# 13-UWB-Antenna.net
KiCad netlist of a schematic drawn in Altium Designer
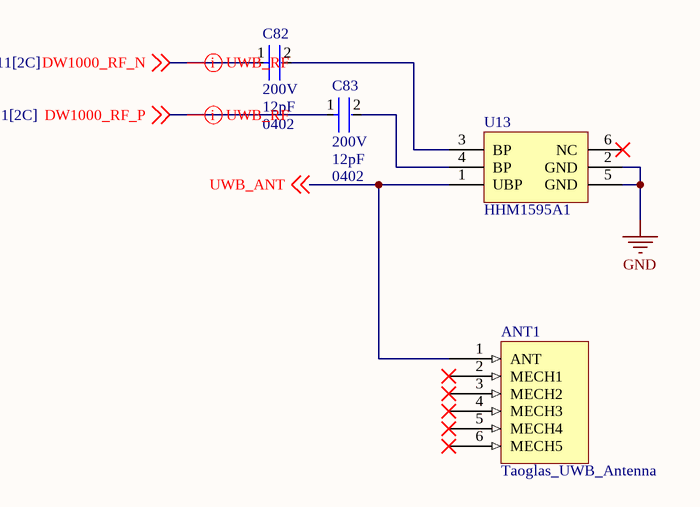
[diagram p0: 13-UWB-Antenna.SchDoc]

(export (version "E")
  (design (tool "Eeschema 10.0.6"))
  (components
    (comp (ref "ANT1")
      (value "Taoglas_UWB_Antenna")
      (footprint "UWC.20 Antenna")
      (libsource (lib "TimeDrive_Lib") (part "Taoglas_UWB_Antenna"))
    )
    (comp (ref "C82")
      (value "GQM1555C2D120FB01D")
      (footprint "FP-GQM155-0_05-MFG")
      (description "Ceramic Capacitor 12pF  ±1% 200VDC C0G 0402 Paper T/R")
      (fields
        (field (name "VOLTAGE RATING (DC)") "200V")
        (field (name "TOLERANCE") "1%")
        (field (name "CAPACITANCE") "12pF")
        (field (name "CASE/PACKAGE") "0402")
      )
      (libsource (lib "Altium Content Vault") (part "11868f565c42a9108669ba33697ecf6"))
    )
    (comp (ref "C83")
      (value "GQM1555C2D120FB01D")
      (footprint "FP-GQM155-0_05-MFG")
      (description "Ceramic Capacitor 12pF  ±1% 200VDC C0G 0402 Paper T/R")
      (fields
        (field (name "VOLTAGE RATING (DC)") "200V")
        (field (name "TOLERANCE") "1%")
        (field (name "CAPACITANCE") "12pF")
        (field (name "CASE/PACKAGE") "0402")
      )
      (libsource (lib "Altium Content Vault") (part "11868f565c42a9108669ba33697ecf6"))
    )
    (comp (ref "U13")
      (value "HHM1595A1")
      (footprint "TDK-HHM1595A1_V")
      (description "Multilayer Balun, 3000 to 8000 MHz, -40 to 85 degC, 6-Pin SMD, RoHS, Tape and Reel")
      (fields (field (name "MANUFACTURER") "TDK"))
      (libsource (lib "Altium Content Vault") (part "TDK-HHM1595A1-6"))
    )
  )
  (nets
    (net (code "1") (name "DW1000_RF_N") (class "Default")
      (node (ref "C82") (pin "1") (pinfunction "1_1") (pintype "passive"))
    )
    (net (code "2") (name "DW1000_RF_P") (class "Default")
      (node (ref "C83") (pin "1") (pinfunction "1_1") (pintype "passive"))
    )
    (net (code "3") (name "GND") (class "Default")
      (node (ref "U13") (pin "2") (pinfunction "GND_2") (pintype "power_in"))
      (node (ref "U13") (pin "5") (pinfunction "GND_5") (pintype "power_in"))
    )
    (net (code "4") (name "Net-(C82-Pad2)") (class "Default")
      (node (ref "C82") (pin "2") (pinfunction "2_2") (pintype "passive"))
      (node (ref "U13") (pin "3") (pinfunction "BP_3") (pintype "passive"))
    )
    (net (code "5") (name "Net-(C83-Pad2)") (class "Default")
      (node (ref "C83") (pin "2") (pinfunction "2_2") (pintype "passive"))
      (node (ref "U13") (pin "4") (pinfunction "BP_4") (pintype "passive"))
    )
    (net (code "6") (name "UWB_ANT") (class "Default")
      (node (ref "ANT1") (pin "1") (pinfunction "ANT_1") (pintype "input"))
      (node (ref "U13") (pin "1") (pinfunction "UBP_1") (pintype "passive"))
    )
    (net (code "7") (name "unconnected-(ANT1-MECH1-Pad2)") (class "Default")
      (node (ref "ANT1") (pin "2") (pinfunction "MECH1_2") (pintype "input+no_connect"))
    )
    (net (code "8") (name "unconnected-(ANT1-MECH2-Pad3)") (class "Default")
      (node (ref "ANT1") (pin "3") (pinfunction "MECH2_3") (pintype "input+no_connect"))
    )
    (net (code "9") (name "unconnected-(ANT1-MECH3-Pad4)") (class "Default")
      (node (ref "ANT1") (pin "4") (pinfunction "MECH3_4") (pintype "input+no_connect"))
    )
    (net (code "10") (name "unconnected-(ANT1-MECH4-Pad5)") (class "Default")
      (node (ref "ANT1") (pin "5") (pinfunction "MECH4_5") (pintype "input+no_connect"))
    )
    (net (code "11") (name "unconnected-(ANT1-MECH5-Pad6)") (class "Default")
      (node (ref "ANT1") (pin "6") (pinfunction "MECH5_6") (pintype "input+no_connect"))
    )
    (net (code "12") (name "unconnected-(U13-NC-Pad6)") (class "Default")
      (node (ref "U13") (pin "6") (pinfunction "NC_6") (pintype "passive+no_connect"))
    )
  )
)
